# BSPDsimp.net
KiCad netlist of a schematic drawn in Altium Designer
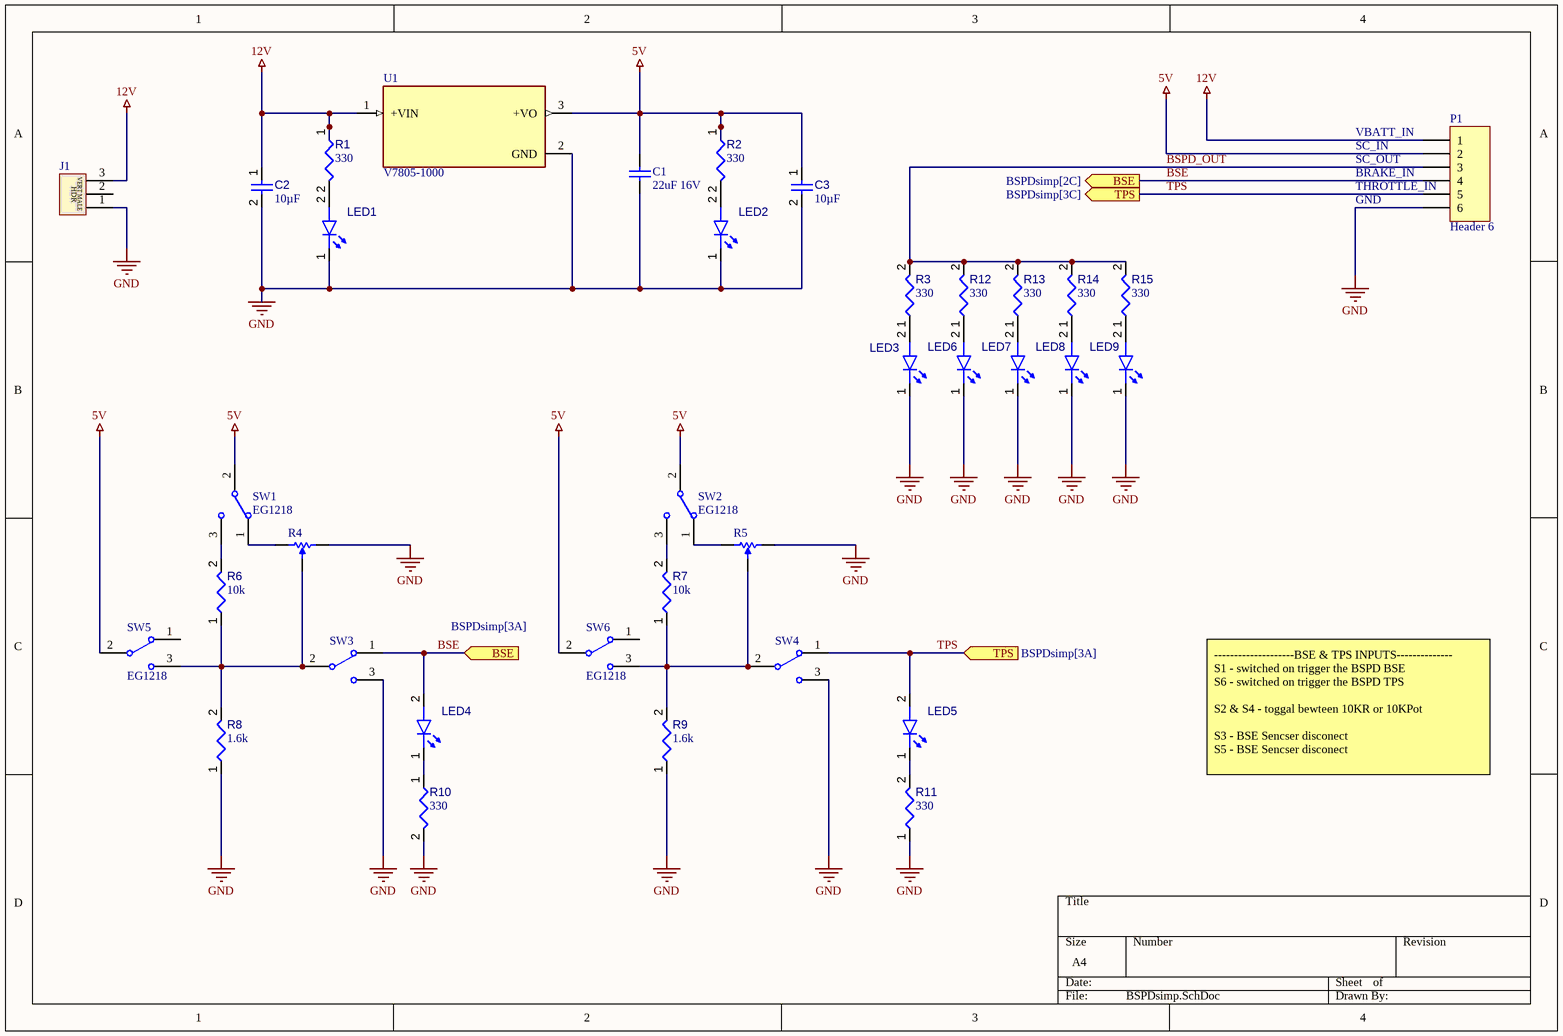
[diagram p0: BSPDsimp.SchDoc]

(export (version "E")
  (design (tool "Eeschema 10.0.6"))
  (components
    (comp (ref "C1")
      (value "22uF 16V")
      (footprint "CAPC2012X14N")
      (description "CAP CER 22UF 16V X5R 0805")
      (libsource (lib "Passive") (part "C-0805-CER-22UF-X5R-16V"))
    )
    (comp (ref "C2")
      (value "10µF")
      (footprint "CAPC2013X135X45NL10T25")
      (description "Chip Capacitor, 10 uF, +/- 10%, 16 V, 0805 (2012 Metric)")
      (fields (field (name "TOLERANCE") "10%") (field (name "Comment") "Capacitor 10 uF +/- 10% 16 V 0805"))
      (libsource (lib "Americas- FSAE- Queens University") (part "CAP-NP-2"))
    )
    (comp (ref "C3")
      (value "10µF")
      (footprint "CAPC2013X135X45NL10T25")
      (description "Chip Capacitor, 10 uF, +/- 10%, 16 V, 0805 (2012 Metric)")
      (fields (field (name "TOLERANCE") "10%") (field (name "Comment") "Capacitor 10 uF +/- 10% 16 V 0805"))
      (libsource (lib "Americas- FSAE- Queens University") (part "CAP-NP-2"))
    )
    (comp (ref "J1")
      (value "HDR-3X1-VERT-2.54MM-1SIDE_SHROUD_1")
      (footprint "HDR-1X3-2.54MM-1SIDE_SHROUD")
      (description "CONN HEADER VERT 3POS 2.54MM")
      (libsource (lib "Americas- FSAE- Queens University") (part "HDR-3X1-VERT-2.54MM-1SIDE_SHROUD_1"))
    )
    (comp (ref "LED1")
      (value "QBLP595-IG")
      (footprint "QTB-QBLP595_V")
      (description "Chip LED 0402, Green, 0.02 A, 3.1 to 3.7 V, -40 to 80 degC, 2-Pin SMD, RoHS, Tape and Reel")
      (libsource (lib "Americas- FSAE- Queens University") (part "LED-KA-2"))
    )
    (comp (ref "LED2")
      (value "QBLP595-IG")
      (footprint "QTB-QBLP595_V")
      (description "Chip LED 0402, Green, 0.02 A, 3.1 to 3.7 V, -40 to 80 degC, 2-Pin SMD, RoHS, Tape and Reel")
      (libsource (lib "Americas- FSAE- Queens University") (part "LED-KA-2"))
    )
    (comp (ref "LED3")
      (value "QBLP595-IG")
      (footprint "QTB-QBLP595_V")
      (description "Chip LED 0402, Green, 0.02 A, 3.1 to 3.7 V, -40 to 80 degC, 2-Pin SMD, RoHS, Tape and Reel")
      (libsource (lib "Americas- FSAE- Queens University") (part "LED-KA-2"))
    )
    (comp (ref "LED4")
      (value "QBLP595-IG")
      (footprint "QTB-QBLP595_V")
      (description "Chip LED 0402, Green, 0.02 A, 3.1 to 3.7 V, -40 to 80 degC, 2-Pin SMD, RoHS, Tape and Reel")
      (libsource (lib "Americas- FSAE- Queens University") (part "LED-KA-2"))
    )
    (comp (ref "LED5")
      (value "QBLP595-IG")
      (footprint "QTB-QBLP595_V")
      (description "Chip LED 0402, Green, 0.02 A, 3.1 to 3.7 V, -40 to 80 degC, 2-Pin SMD, RoHS, Tape and Reel")
      (libsource (lib "Americas- FSAE- Queens University") (part "LED-KA-2"))
    )
    (comp (ref "LED6")
      (value "QBLP595-IG")
      (footprint "QTB-QBLP595_V")
      (description "Chip LED 0402, Green, 0.02 A, 3.1 to 3.7 V, -40 to 80 degC, 2-Pin SMD, RoHS, Tape and Reel")
      (libsource (lib "Americas- FSAE- Queens University") (part "LED-KA-2"))
    )
    (comp (ref "LED7")
      (value "QBLP595-IG")
      (footprint "QTB-QBLP595_V")
      (description "Chip LED 0402, Green, 0.02 A, 3.1 to 3.7 V, -40 to 80 degC, 2-Pin SMD, RoHS, Tape and Reel")
      (libsource (lib "Americas- FSAE- Queens University") (part "LED-KA-2"))
    )
    (comp (ref "LED8")
      (value "QBLP595-IG")
      (footprint "QTB-QBLP595_V")
      (description "Chip LED 0402, Green, 0.02 A, 3.1 to 3.7 V, -40 to 80 degC, 2-Pin SMD, RoHS, Tape and Reel")
      (libsource (lib "Americas- FSAE- Queens University") (part "LED-KA-2"))
    )
    (comp (ref "LED9")
      (value "QBLP595-IG")
      (footprint "QTB-QBLP595_V")
      (description "Chip LED 0402, Green, 0.02 A, 3.1 to 3.7 V, -40 to 80 degC, 2-Pin SMD, RoHS, Tape and Reel")
      (libsource (lib "Americas- FSAE- Queens University") (part "LED-KA-2"))
    )
    (comp (ref "P1")
      (value "Header 6")
      (footprint "HDR1X6")
      (description "Header, 6-Pin")
      (fields (field (name "PUBLISHER") "Altium Limited"))
      (libsource (lib "Miscellaneous Connectors") (part "Header 6"))
    )
    (comp (ref "R1")
      (value "330")
      (footprint "RESC0402(1005)_L")
      (description "330R 0.063W 5% 0402 (1005 Metric)  SMD")
      (fields (field (name "TOLERANCE") "5%") (field (name "POWER") "63mW"))
      (libsource (lib "Americas- FSAE- Queens University") (part "330R2J"))
    )
    (comp (ref "R2")
      (value "330")
      (footprint "RESC0402(1005)_L")
      (description "330R 0.063W 5% 0402 (1005 Metric)  SMD")
      (fields (field (name "TOLERANCE") "5%") (field (name "POWER") "63mW"))
      (libsource (lib "Americas- FSAE- Queens University") (part "330R2J"))
    )
    (comp (ref "R3")
      (value "330")
      (footprint "RESC0402(1005)_L")
      (description "330R 0.063W 5% 0402 (1005 Metric)  SMD")
      (fields (field (name "TOLERANCE") "5%") (field (name "POWER") "63mW"))
      (libsource (lib "Americas- FSAE- Queens University") (part "330R2J"))
    )
    (comp (ref "R4")
      (value "35WR10KLFTR")
      (footprint "BI-35WR10KLFTR-3_V")
      (fields
        (field (name "MANUFACTURER") "BI Technologies")
        (field (name "POWER") "100mW")
        (field (name "TOLERANCE") "25%")
      )
      (libsource (lib "Americas- FSAE- Queens University") (part "RES-ADJ-3_A"))
    )
    (comp (ref "R5")
      (value "35WR10KLFTR")
      (footprint "BI-35WR10KLFTR-3_V")
      (fields
        (field (name "MANUFACTURER") "BI Technologies")
        (field (name "POWER") "100mW")
        (field (name "TOLERANCE") "25%")
      )
      (libsource (lib "Americas- FSAE- Queens University") (part "RES-ADJ-3_A"))
    )
    (comp (ref "R6")
      (value "10k")
      (footprint "RESC0402(1005)_L")
      (description "10K 0.063W 1% 0402 (1005 Metric)  SMD")
      (fields (field (name "POWER") "63mW") (field (name "TOLERANCE") "1%"))
      (libsource (lib "Americas- FSAE- Queens University") (part "10KR2F"))
    )
    (comp (ref "R7")
      (value "10k")
      (footprint "RESC0402(1005)_L")
      (description "10K 0.063W 1% 0402 (1005 Metric)  SMD")
      (fields (field (name "POWER") "63mW") (field (name "TOLERANCE") "1%"))
      (libsource (lib "Americas- FSAE- Queens University") (part "10KR2F"))
    )
    (comp (ref "R8")
      (value "1.6k")
      (footprint "RESC0402(1005)_L")
      (description "1K6 0.063W 5% 0402 (1005 Metric)  SMD")
      (fields (field (name "TOLERANCE") "5%") (field (name "POWER") "63mW"))
      (libsource (lib "Americas- FSAE- Queens University") (part "1D6KR2J"))
    )
    (comp (ref "R9")
      (value "1.6k")
      (footprint "RESC0402(1005)_L")
      (description "1K6 0.063W 5% 0402 (1005 Metric)  SMD")
      (fields (field (name "TOLERANCE") "5%") (field (name "POWER") "63mW"))
      (libsource (lib "Americas- FSAE- Queens University") (part "1D6KR2J"))
    )
    (comp (ref "R10")
      (value "330")
      (footprint "RESC0402(1005)_L")
      (description "330R 0.063W 5% 0402 (1005 Metric)  SMD")
      (fields (field (name "TOLERANCE") "5%") (field (name "POWER") "63mW"))
      (libsource (lib "Americas- FSAE- Queens University") (part "330R2J"))
    )
    (comp (ref "R11")
      (value "330")
      (footprint "RESC0402(1005)_L")
      (description "330R 0.063W 5% 0402 (1005 Metric)  SMD")
      (fields (field (name "TOLERANCE") "5%") (field (name "POWER") "63mW"))
      (libsource (lib "Americas- FSAE- Queens University") (part "330R2J"))
    )
    (comp (ref "R12")
      (value "330")
      (footprint "RESC0402(1005)_L")
      (description "330R 0.063W 5% 0402 (1005 Metric)  SMD")
      (fields (field (name "TOLERANCE") "5%") (field (name "POWER") "63mW"))
      (libsource (lib "Americas- FSAE- Queens University") (part "330R2J"))
    )
    (comp (ref "R13")
      (value "330")
      (footprint "RESC0402(1005)_L")
      (description "330R 0.063W 5% 0402 (1005 Metric)  SMD")
      (fields (field (name "TOLERANCE") "5%") (field (name "POWER") "63mW"))
      (libsource (lib "Americas- FSAE- Queens University") (part "330R2J"))
    )
    (comp (ref "R14")
      (value "330")
      (footprint "RESC0402(1005)_L")
      (description "330R 0.063W 5% 0402 (1005 Metric)  SMD")
      (fields (field (name "TOLERANCE") "5%") (field (name "POWER") "63mW"))
      (libsource (lib "Americas- FSAE- Queens University") (part "330R2J"))
    )
    (comp (ref "R15")
      (value "330")
      (footprint "RESC0402(1005)_L")
      (description "330R 0.063W 5% 0402 (1005 Metric)  SMD")
      (fields (field (name "TOLERANCE") "5%") (field (name "POWER") "63mW"))
      (libsource (lib "Americas- FSAE- Queens University") (part "330R2J"))
    )
    (comp (ref "SW1")
      (value "EG1218")
      (footprint "ESWI-EG1218_V")
      (description "Slide Switch, SPDT, 500 V, -20 to 70 degC, 3-Pin THD, RoHS, Bulk")
      (fields (field (name "MANUFACTURER") "E-Switch"))
      (libsource (lib "Americas- FSAE- Queens University") (part "SW-SPDT-3_B"))
    )
    (comp (ref "SW2")
      (value "EG1218")
      (footprint "ESWI-EG1218_V")
      (description "Slide Switch, SPDT, 500 V, -20 to 70 degC, 3-Pin THD, RoHS, Bulk")
      (fields (field (name "MANUFACTURER") "E-Switch"))
      (libsource (lib "Americas- FSAE- Queens University") (part "SW-SPDT-3_B"))
    )
    (comp (ref "SW3")
      (value "EG1218")
      (footprint "ESWI-EG1218_V")
      (description "Slide Switch, SPDT, 500 V, -20 to 70 degC, 3-Pin THD, RoHS, Bulk")
      (fields (field (name "MANUFACTURER") "E-Switch"))
      (libsource (lib "Americas- FSAE- Queens University") (part "SW-SPDT-3_B"))
    )
    (comp (ref "SW4")
      (value "EG1218")
      (footprint "ESWI-EG1218_V")
      (description "Slide Switch, SPDT, 500 V, -20 to 70 degC, 3-Pin THD, RoHS, Bulk")
      (fields (field (name "MANUFACTURER") "E-Switch"))
      (libsource (lib "Americas- FSAE- Queens University") (part "SW-SPDT-3_B"))
    )
    (comp (ref "SW5")
      (value "EG1218")
      (footprint "ESWI-EG1218_V")
      (description "Slide Switch, SPDT, 500 V, -20 to 70 degC, 3-Pin THD, RoHS, Bulk")
      (fields (field (name "MANUFACTURER") "E-Switch"))
      (libsource (lib "Americas- FSAE- Queens University") (part "SW-SPDT-3_B"))
    )
    (comp (ref "SW6")
      (value "EG1218")
      (footprint "ESWI-EG1218_V")
      (description "Slide Switch, SPDT, 500 V, -20 to 70 degC, 3-Pin THD, RoHS, Bulk")
      (fields (field (name "MANUFACTURER") "E-Switch"))
      (libsource (lib "Americas- FSAE- Queens University") (part "SW-SPDT-3_B"))
    )
    (comp (ref "U1")
      (value "V7805-1000")
      (footprint "CONV_V7805-1000")
      (description "3.3 Vdc, 1 A, 1.65 W, 4.5~28 Vdc Input Range")
      (fields (field (name "MF") "{'manufacturer': u'CUI'}"))
      (libsource (lib "V7805-1000") (part "V7805-1000"))
    )
  )
  (nets
    (net (code "2") (name "/BSE") (class "Default")
      (node (ref "LED4") (pin "2") (pinfunction "A_2") (pintype "passive"))
      (node (ref "P1") (pin "4") (pinfunction "4_4") (pintype "passive"))
      (node (ref "SW3") (pin "1") (pinfunction "1_1") (pintype "passive"))
    )
    (net (code "3") (name "/BSPD_OUT") (class "Default")
      (node (ref "P1") (pin "3") (pinfunction "3_3") (pintype "passive"))
      (node (ref "R12") (pin "2") (pinfunction "2_2") (pintype "passive"))
      (node (ref "R13") (pin "2") (pinfunction "2_2") (pintype "passive"))
      (node (ref "R14") (pin "2") (pinfunction "2_2") (pintype "passive"))
      (node (ref "R15") (pin "2") (pinfunction "2_2") (pintype "passive"))
      (node (ref "R3") (pin "2") (pinfunction "2_2") (pintype "passive"))
    )
    (net (code "4") (name "/TPS") (class "Default")
      (node (ref "LED5") (pin "2") (pinfunction "A_2") (pintype "passive"))
      (node (ref "P1") (pin "5") (pinfunction "5_5") (pintype "passive"))
      (node (ref "SW4") (pin "1") (pinfunction "1_1") (pintype "passive"))
    )
    (net (code "5") (name "5V") (class "Default")
      (node (ref "C1") (pin "2") (pinfunction "2_2") (pintype "passive"))
      (node (ref "C3") (pin "1") (pinfunction "1_1") (pintype "passive"))
      (node (ref "P1") (pin "2") (pinfunction "2_2") (pintype "passive"))
      (node (ref "R2") (pin "1") (pinfunction "1_1") (pintype "passive"))
      (node (ref "SW1") (pin "2") (pinfunction "COM_2") (pintype "passive"))
      (node (ref "SW2") (pin "2") (pinfunction "COM_2") (pintype "passive"))
      (node (ref "SW5") (pin "2") (pinfunction "COM_2") (pintype "passive"))
      (node (ref "SW6") (pin "2") (pinfunction "COM_2") (pintype "passive"))
      (node (ref "U1") (pin "3") (pinfunction "+VO_3") (pintype "output"))
    )
    (net (code "6") (name "12V") (class "Default")
      (node (ref "C2") (pin "1") (pinfunction "1_1") (pintype "passive"))
      (node (ref "J1") (pin "3") (pintype "passive"))
      (node (ref "P1") (pin "1") (pinfunction "1_1") (pintype "passive"))
      (node (ref "R1") (pin "1") (pinfunction "1_1") (pintype "passive"))
      (node (ref "U1") (pin "1") (pinfunction "+VIN_1") (pintype "input"))
    )
    (net (code "7") (name "GND") (class "Default")
      (node (ref "C1") (pin "1") (pinfunction "1_1") (pintype "passive"))
      (node (ref "C2") (pin "2") (pinfunction "2_2") (pintype "passive"))
      (node (ref "C3") (pin "2") (pinfunction "2_2") (pintype "passive"))
      (node (ref "J1") (pin "1") (pintype "passive"))
      (node (ref "LED1") (pin "1") (pinfunction "K_1") (pintype "passive"))
      (node (ref "LED2") (pin "1") (pinfunction "K_1") (pintype "passive"))
      (node (ref "LED3") (pin "1") (pinfunction "K_1") (pintype "passive"))
      (node (ref "LED6") (pin "1") (pinfunction "K_1") (pintype "passive"))
      (node (ref "LED7") (pin "1") (pinfunction "K_1") (pintype "passive"))
      (node (ref "LED8") (pin "1") (pinfunction "K_1") (pintype "passive"))
      (node (ref "LED9") (pin "1") (pinfunction "K_1") (pintype "passive"))
      (node (ref "P1") (pin "6") (pinfunction "6_6") (pintype "passive"))
      (node (ref "R10") (pin "2") (pinfunction "2_2") (pintype "passive"))
      (node (ref "R11") (pin "1") (pinfunction "1_1") (pintype "passive"))
      (node (ref "R4") (pin "3") (pinfunction "3_3") (pintype "passive"))
      (node (ref "R5") (pin "3") (pinfunction "3_3") (pintype "passive"))
      (node (ref "R8") (pin "1") (pinfunction "1_1") (pintype "passive"))
      (node (ref "R9") (pin "1") (pinfunction "1_1") (pintype "passive"))
      (node (ref "SW3") (pin "3") (pinfunction "3_3") (pintype "passive"))
      (node (ref "SW4") (pin "3") (pinfunction "3_3") (pintype "passive"))
      (node (ref "U1") (pin "2") (pinfunction "GND_2") (pintype "power_in"))
    )
    (net (code "8") (name "Net-(LED1-A)") (class "Default")
      (node (ref "LED1") (pin "2") (pinfunction "A_2") (pintype "passive"))
      (node (ref "R1") (pin "2") (pinfunction "2_2") (pintype "passive"))
    )
    (net (code "9") (name "Net-(LED2-A)") (class "Default")
      (node (ref "LED2") (pin "2") (pinfunction "A_2") (pintype "passive"))
      (node (ref "R2") (pin "2") (pinfunction "2_2") (pintype "passive"))
    )
    (net (code "10") (name "Net-(LED3-A)") (class "Default")
      (node (ref "LED3") (pin "2") (pinfunction "A_2") (pintype "passive"))
      (node (ref "R15") (pin "1") (pinfunction "1_1") (pintype "passive"))
    )
    (net (code "11") (name "Net-(LED4-K)") (class "Default")
      (node (ref "LED4") (pin "1") (pinfunction "K_1") (pintype "passive"))
      (node (ref "R10") (pin "1") (pinfunction "1_1") (pintype "passive"))
    )
    (net (code "12") (name "Net-(LED5-K)") (class "Default")
      (node (ref "LED5") (pin "1") (pinfunction "K_1") (pintype "passive"))
      (node (ref "R11") (pin "2") (pinfunction "2_2") (pintype "passive"))
    )
    (net (code "13") (name "Net-(LED6-A)") (class "Default")
      (node (ref "LED6") (pin "2") (pinfunction "A_2") (pintype "passive"))
      (node (ref "R3") (pin "1") (pinfunction "1_1") (pintype "passive"))
    )
    (net (code "14") (name "Net-(LED7-A)") (class "Default")
      (node (ref "LED7") (pin "2") (pinfunction "A_2") (pintype "passive"))
      (node (ref "R12") (pin "1") (pinfunction "1_1") (pintype "passive"))
    )
    (net (code "15") (name "Net-(LED8-A)") (class "Default")
      (node (ref "LED8") (pin "2") (pinfunction "A_2") (pintype "passive"))
      (node (ref "R13") (pin "1") (pinfunction "1_1") (pintype "passive"))
    )
    (net (code "16") (name "Net-(LED9-A)") (class "Default")
      (node (ref "LED9") (pin "2") (pinfunction "A_2") (pintype "passive"))
      (node (ref "R14") (pin "1") (pinfunction "1_1") (pintype "passive"))
    )
    (net (code "17") (name "Net-(R4-Pad1)") (class "Default")
      (node (ref "R4") (pin "1") (pinfunction "1_1") (pintype "passive"))
      (node (ref "SW1") (pin "1") (pinfunction "1_1") (pintype "passive"))
    )
    (net (code "18") (name "Net-(R5-Pad1)") (class "Default")
      (node (ref "R5") (pin "1") (pinfunction "1_1") (pintype "passive"))
      (node (ref "SW2") (pin "1") (pinfunction "1_1") (pintype "passive"))
    )
    (net (code "19") (name "Net-(R6-Pad2)") (class "Default")
      (node (ref "R6") (pin "2") (pinfunction "2_2") (pintype "passive"))
      (node (ref "SW1") (pin "3") (pinfunction "3_3") (pintype "passive"))
    )
    (net (code "20") (name "Net-(R7-Pad2)") (class "Default")
      (node (ref "R7") (pin "2") (pinfunction "2_2") (pintype "passive"))
      (node (ref "SW2") (pin "3") (pinfunction "3_3") (pintype "passive"))
    )
    (net (code "21") (name "Net-(SW3-COM)") (class "Default")
      (node (ref "R4") (pin "2") (pinfunction "2_2") (pintype "passive"))
      (node (ref "R6") (pin "1") (pinfunction "1_1") (pintype "passive"))
      (node (ref "R8") (pin "2") (pinfunction "2_2") (pintype "passive"))
      (node (ref "SW3") (pin "2") (pinfunction "COM_2") (pintype "passive"))
      (node (ref "SW5") (pin "3") (pinfunction "3_3") (pintype "passive"))
    )
    (net (code "22") (name "Net-(SW4-COM)") (class "Default")
      (node (ref "R5") (pin "2") (pinfunction "2_2") (pintype "passive"))
      (node (ref "R7") (pin "1") (pinfunction "1_1") (pintype "passive"))
      (node (ref "R9") (pin "2") (pinfunction "2_2") (pintype "passive"))
      (node (ref "SW4") (pin "2") (pinfunction "COM_2") (pintype "passive"))
      (node (ref "SW6") (pin "3") (pinfunction "3_3") (pintype "passive"))
    )
    (net (code "23") (name "unconnected-(J1-Pad2)") (class "Default")
      (node (ref "J1") (pin "2") (pintype "passive"))
    )
    (net (code "24") (name "unconnected-(SW5-Pad1)") (class "Default")
      (node (ref "SW5") (pin "1") (pinfunction "1_1") (pintype "passive"))
    )
    (net (code "25") (name "unconnected-(SW6-Pad1)") (class "Default")
      (node (ref "SW6") (pin "1") (pinfunction "1_1") (pintype "passive"))
    )
  )
)
